# ResponseBoxBncBreakOutV2.net
KiCad netlist of a schematic drawn in EAGLE
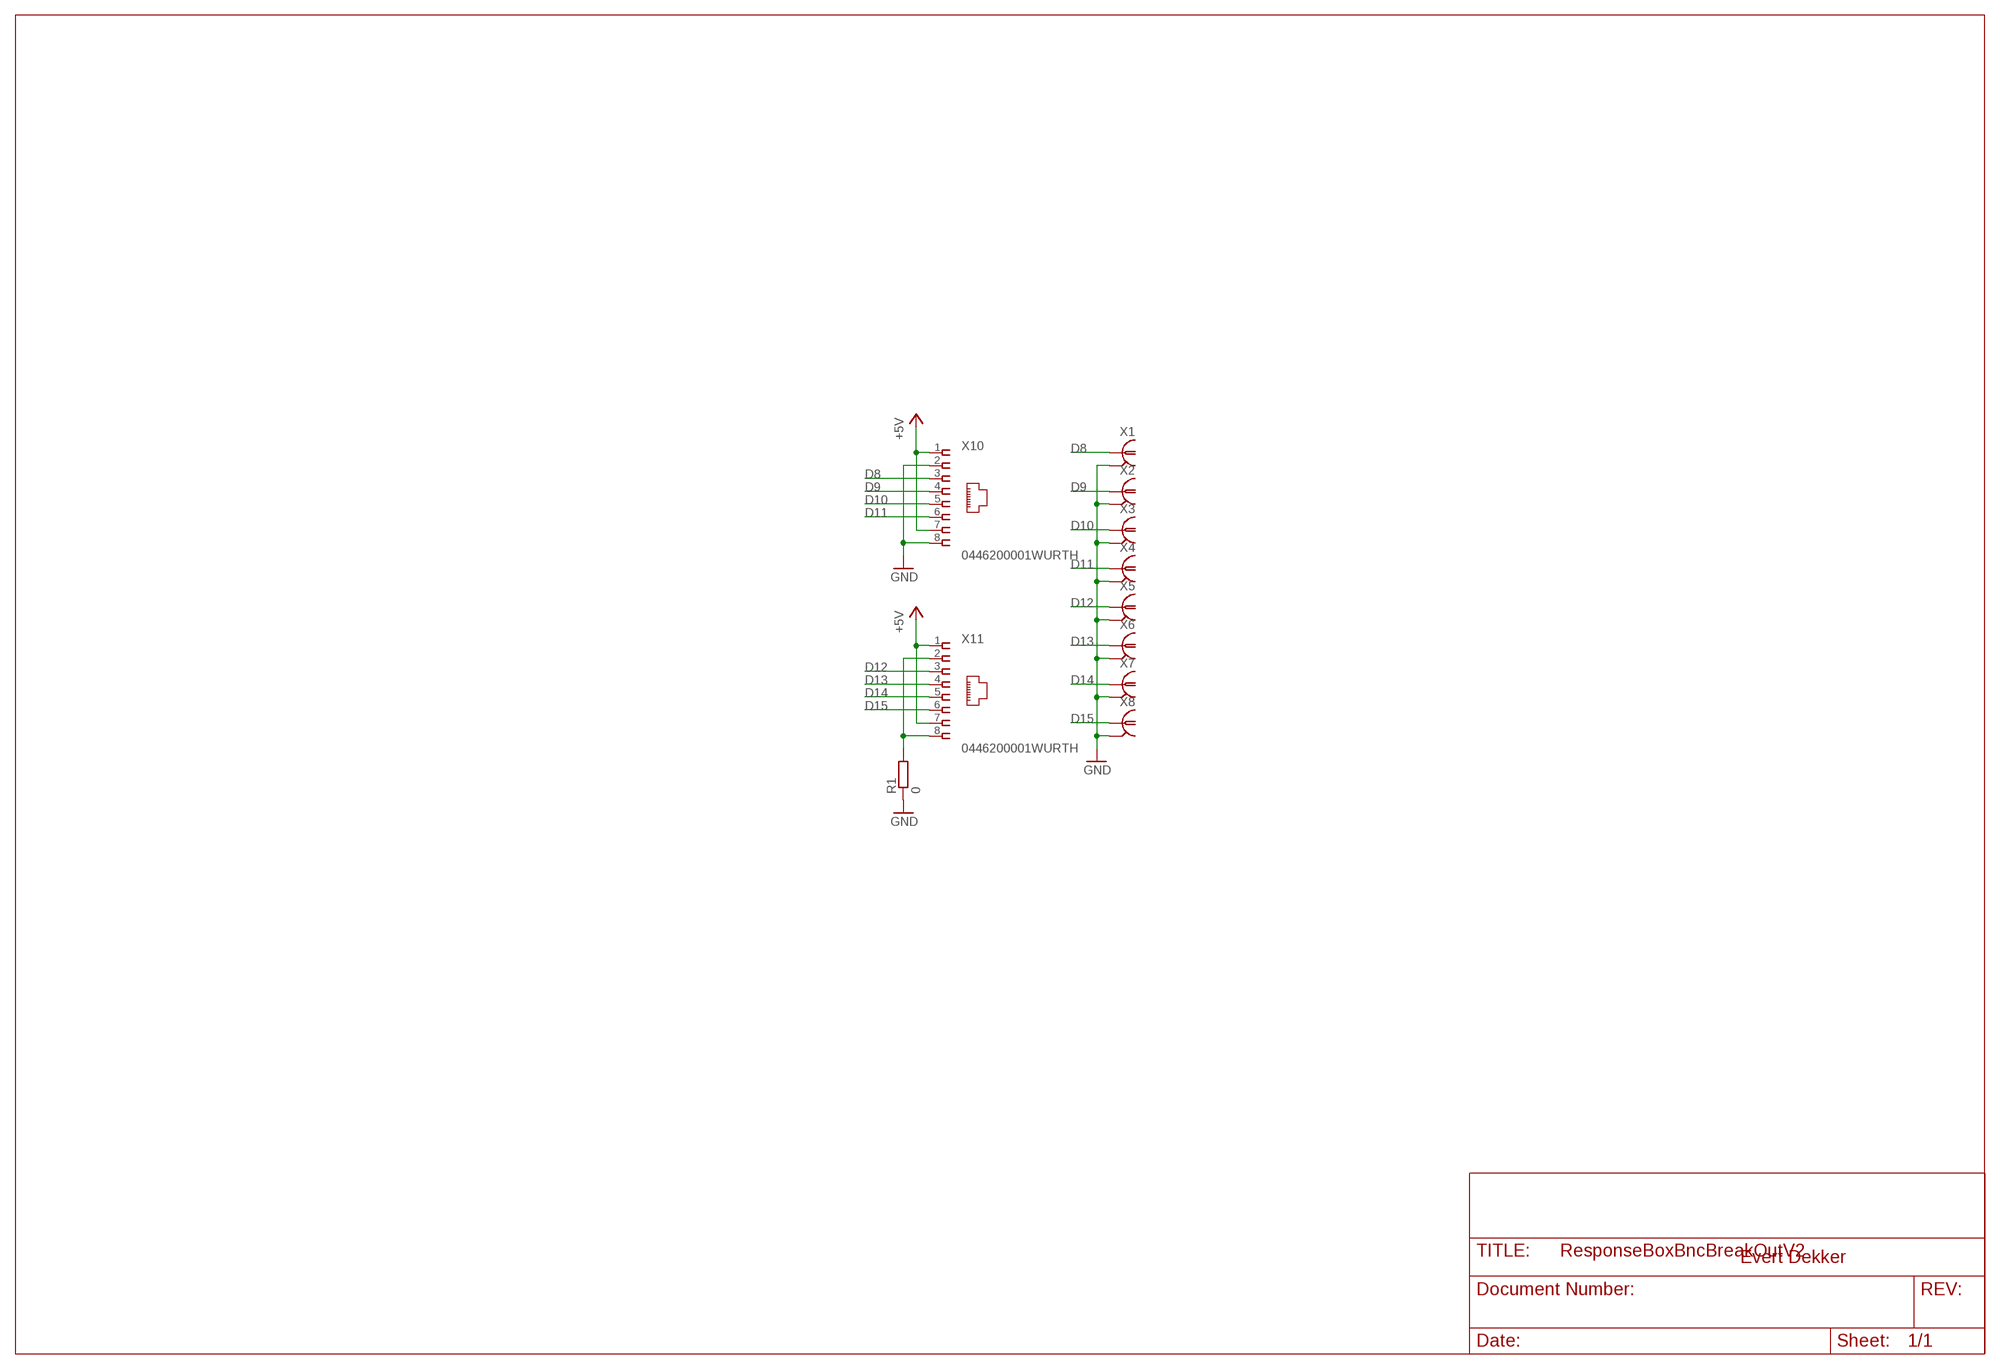
[diagram p0: schematic, sheet 1]

(export (version "E")
  (design (tool "Eeschema 10.0.6"))
  (components
    (comp (ref "R1")
      (value "0")
      (footprint "eagle-import:M0805")
      (libsource (lib "eagle-import") (part "R-EU_M0805"))
    )
    (comp (ref "X1")
      (value "R141426")
      (footprint "eagle-import:R141426")
      (fields (field (name "MF") "FARNELL") (field (name "MPN") "R141426161"))
      (libsource (lib "eagle-import") (part "R141426"))
    )
    (comp (ref "X2")
      (value "R141426")
      (footprint "eagle-import:R141426")
      (fields (field (name "MF") "FARNELL") (field (name "MPN") "R141426161"))
      (libsource (lib "eagle-import") (part "R141426"))
    )
    (comp (ref "X3")
      (value "R141426")
      (footprint "eagle-import:R141426")
      (fields (field (name "MF") "FARNELL") (field (name "MPN") "R141426161"))
      (libsource (lib "eagle-import") (part "R141426"))
    )
    (comp (ref "X4")
      (value "R141426")
      (footprint "eagle-import:R141426")
      (fields (field (name "MF") "FARNELL") (field (name "MPN") "R141426161"))
      (libsource (lib "eagle-import") (part "R141426"))
    )
    (comp (ref "X5")
      (value "R141426")
      (footprint "eagle-import:R141426")
      (fields (field (name "MF") "FARNELL") (field (name "MPN") "R141426161"))
      (libsource (lib "eagle-import") (part "R141426"))
    )
    (comp (ref "X6")
      (value "R141426")
      (footprint "eagle-import:R141426")
      (fields (field (name "MF") "FARNELL") (field (name "MPN") "R141426161"))
      (libsource (lib "eagle-import") (part "R141426"))
    )
    (comp (ref "X7")
      (value "R141426")
      (footprint "eagle-import:R141426")
      (fields (field (name "MF") "FARNELL") (field (name "MPN") "R141426161"))
      (libsource (lib "eagle-import") (part "R141426"))
    )
    (comp (ref "X8")
      (value "R141426")
      (footprint "eagle-import:R141426")
      (fields (field (name "MF") "FARNELL") (field (name "MPN") "R141426161"))
      (libsource (lib "eagle-import") (part "R141426"))
    )
    (comp (ref "X10")
      (value "0446200001WURTH")
      (footprint "eagle-import:WURTH-WR-MJ")
      (libsource (lib "eagle-import") (part "0446200001WURTH"))
    )
    (comp (ref "X11")
      (value "0446200001WURTH")
      (footprint "eagle-import:WURTH-WR-MJ")
      (libsource (lib "eagle-import") (part "0446200001WURTH"))
    )
  )
  (nets
    (net (code "1") (name "+5V") (class "Default")
      (node (ref "X10") (pin "1") (pinfunction "1_1") (pintype "passive"))
      (node (ref "X10") (pin "7") (pinfunction "7_7") (pintype "passive"))
      (node (ref "X11") (pin "1") (pinfunction "1_1") (pintype "passive"))
      (node (ref "X11") (pin "7") (pinfunction "7_7") (pintype "passive"))
    )
    (net (code "2") (name "/D8") (class "Default")
      (node (ref "X1") (pin "1") (pinfunction "1_1") (pintype "passive"))
      (node (ref "X10") (pin "3") (pinfunction "3_3") (pintype "passive"))
    )
    (net (code "3") (name "/D9") (class "Default")
      (node (ref "X10") (pin "4") (pinfunction "4_4") (pintype "passive"))
      (node (ref "X2") (pin "1") (pinfunction "1_1") (pintype "passive"))
    )
    (net (code "4") (name "/D10") (class "Default")
      (node (ref "X10") (pin "5") (pinfunction "5_5") (pintype "passive"))
      (node (ref "X3") (pin "1") (pinfunction "1_1") (pintype "passive"))
    )
    (net (code "5") (name "/D11") (class "Default")
      (node (ref "X10") (pin "6") (pinfunction "6_6") (pintype "passive"))
      (node (ref "X4") (pin "1") (pinfunction "1_1") (pintype "passive"))
    )
    (net (code "6") (name "/D12") (class "Default")
      (node (ref "X11") (pin "3") (pinfunction "3_3") (pintype "passive"))
      (node (ref "X5") (pin "1") (pinfunction "1_1") (pintype "passive"))
    )
    (net (code "7") (name "/D13") (class "Default")
      (node (ref "X11") (pin "4") (pinfunction "4_4") (pintype "passive"))
      (node (ref "X6") (pin "1") (pinfunction "1_1") (pintype "passive"))
    )
    (net (code "8") (name "/D14") (class "Default")
      (node (ref "X11") (pin "5") (pinfunction "5_5") (pintype "passive"))
      (node (ref "X7") (pin "1") (pinfunction "1_1") (pintype "passive"))
    )
    (net (code "9") (name "/D15") (class "Default")
      (node (ref "X11") (pin "6") (pinfunction "6_6") (pintype "passive"))
      (node (ref "X8") (pin "1") (pinfunction "1_1") (pintype "passive"))
    )
    (net (code "10") (name "GND") (class "Default")
      (node (ref "R1") (pin "1") (pinfunction "1_1") (pintype "passive"))
      (node (ref "X1") (pin "2") (pinfunction "2_2") (pintype "passive"))
      (node (ref "X1") (pin "3") (pinfunction "2_3") (pintype "passive"))
      (node (ref "X1") (pin "4") (pinfunction "2_4") (pintype "passive"))
      (node (ref "X1") (pin "5") (pinfunction "2_5") (pintype "passive"))
      (node (ref "X10") (pin "2") (pinfunction "2_2") (pintype "passive"))
      (node (ref "X10") (pin "8") (pinfunction "8_8") (pintype "passive"))
      (node (ref "X2") (pin "2") (pinfunction "2_2") (pintype "passive"))
      (node (ref "X2") (pin "3") (pinfunction "2_3") (pintype "passive"))
      (node (ref "X2") (pin "4") (pinfunction "2_4") (pintype "passive"))
      (node (ref "X2") (pin "5") (pinfunction "2_5") (pintype "passive"))
      (node (ref "X3") (pin "2") (pinfunction "2_2") (pintype "passive"))
      (node (ref "X3") (pin "3") (pinfunction "2_3") (pintype "passive"))
      (node (ref "X3") (pin "4") (pinfunction "2_4") (pintype "passive"))
      (node (ref "X3") (pin "5") (pinfunction "2_5") (pintype "passive"))
      (node (ref "X4") (pin "2") (pinfunction "2_2") (pintype "passive"))
      (node (ref "X4") (pin "3") (pinfunction "2_3") (pintype "passive"))
      (node (ref "X4") (pin "4") (pinfunction "2_4") (pintype "passive"))
      (node (ref "X4") (pin "5") (pinfunction "2_5") (pintype "passive"))
      (node (ref "X5") (pin "2") (pinfunction "2_2") (pintype "passive"))
      (node (ref "X5") (pin "3") (pinfunction "2_3") (pintype "passive"))
      (node (ref "X5") (pin "4") (pinfunction "2_4") (pintype "passive"))
      (node (ref "X5") (pin "5") (pinfunction "2_5") (pintype "passive"))
      (node (ref "X6") (pin "2") (pinfunction "2_2") (pintype "passive"))
      (node (ref "X6") (pin "3") (pinfunction "2_3") (pintype "passive"))
      (node (ref "X6") (pin "4") (pinfunction "2_4") (pintype "passive"))
      (node (ref "X6") (pin "5") (pinfunction "2_5") (pintype "passive"))
      (node (ref "X7") (pin "2") (pinfunction "2_2") (pintype "passive"))
      (node (ref "X7") (pin "3") (pinfunction "2_3") (pintype "passive"))
      (node (ref "X7") (pin "4") (pinfunction "2_4") (pintype "passive"))
      (node (ref "X7") (pin "5") (pinfunction "2_5") (pintype "passive"))
      (node (ref "X8") (pin "2") (pinfunction "2_2") (pintype "passive"))
      (node (ref "X8") (pin "3") (pinfunction "2_3") (pintype "passive"))
      (node (ref "X8") (pin "4") (pinfunction "2_4") (pintype "passive"))
      (node (ref "X8") (pin "5") (pinfunction "2_5") (pintype "passive"))
    )
    (net (code "11") (name "Net-(R1-Pad2)") (class "Default")
      (node (ref "R1") (pin "2") (pinfunction "2_2") (pintype "passive"))
      (node (ref "X11") (pin "2") (pinfunction "2_2") (pintype "passive"))
      (node (ref "X11") (pin "8") (pinfunction "8_8") (pintype "passive"))
    )
  )
)
